# CameraSmartWatch.net
KiCad netlist of a schematic drawn in EasyEDA Pro
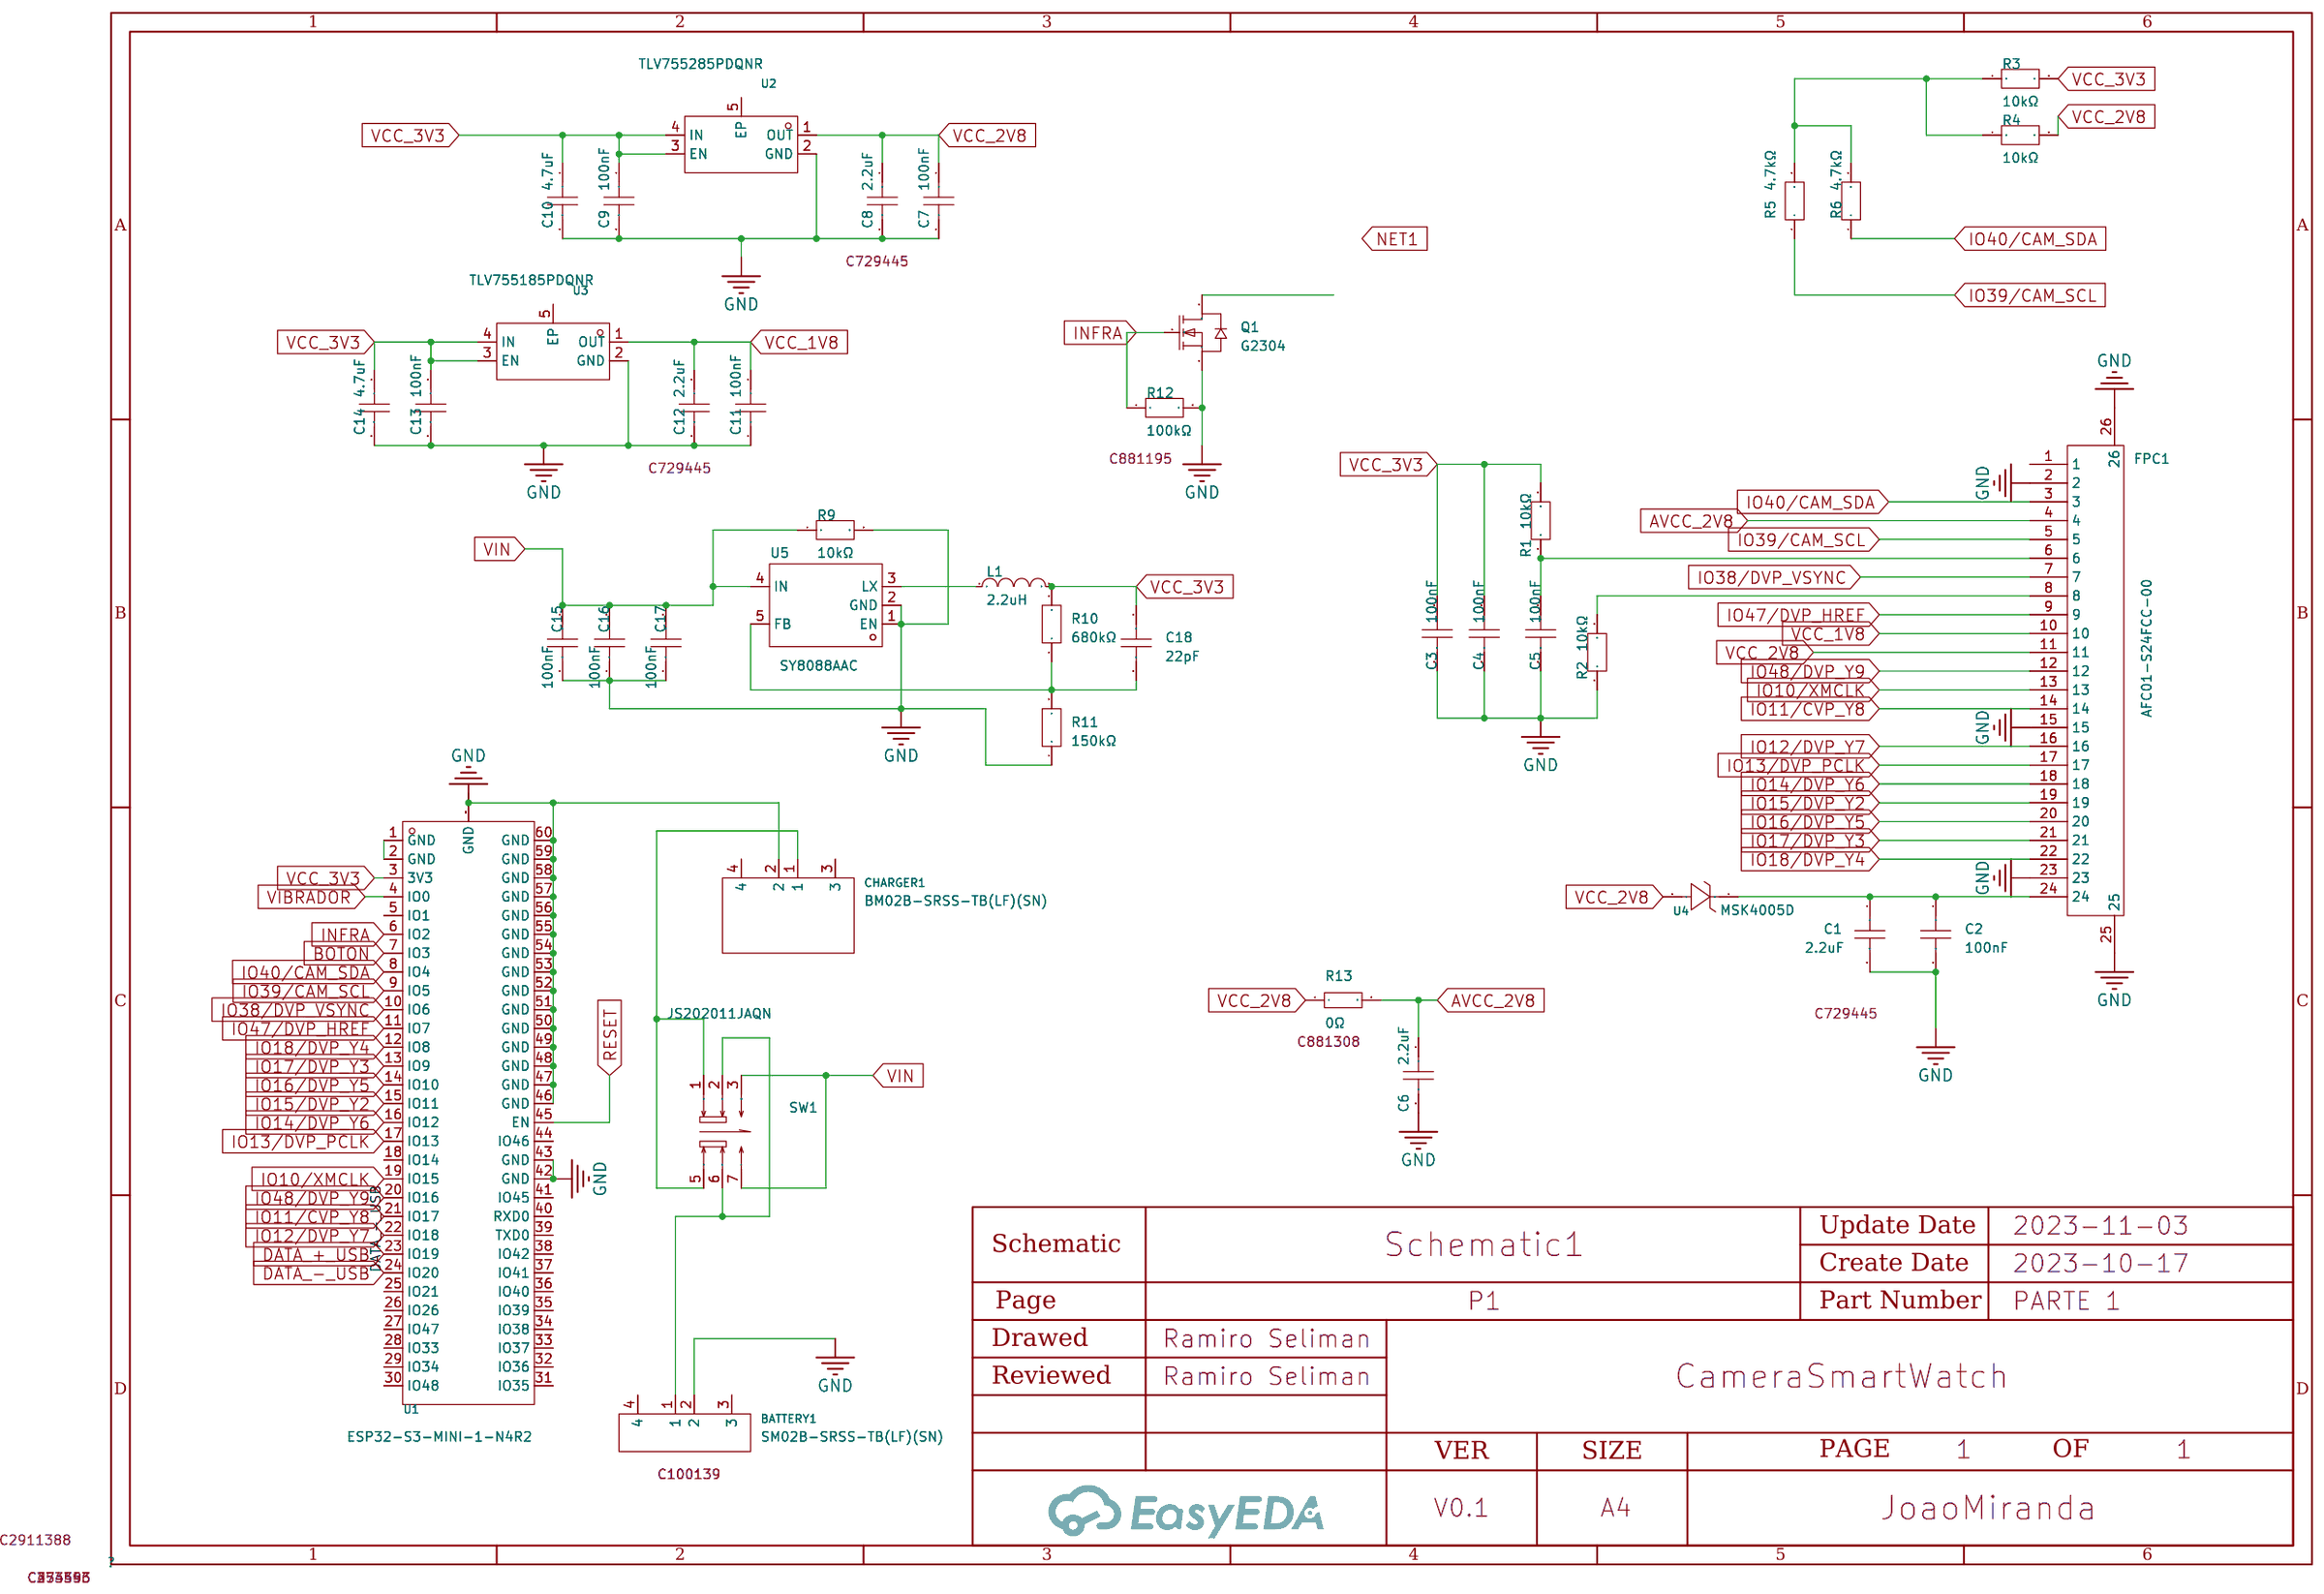
[diagram p0: schematic sheet]

(export (version "E")
  (design (tool "Eeschema 10.0.6"))
  (components
    (comp (ref "BATTERY1")
      (value "SM02B-SRSS-TB(LF)(SN)")
      (footprint "easyedapro:CONN-SMD_2P-P1.00_SM02B-SRSS-TB-LF-SN")
      (fields (field (name "Manufacturer") "JST"))
      (libsource (lib "easyedapro") (part "SM02B-SRSS-TB (LF)(SN)"))
    )
    (comp (ref "C1")
      (value "2.2uF")
      (footprint "easyedapro:C0201")
      (fields
        (field (name "Manufacturer Part") "C0201X5R225M100NT")
        (field (name "Manufacturer") "SANYEAR(叁叶源)")
        (field (name "Supplier Part") "C729445")
      )
      (libsource (lib "easyedapro") (part "CAP"))
    )
    (comp (ref "C2")
      (value "100nF")
      (footprint "easyedapro:C0201")
      (fields
        (field (name "Manufacturer Part") "C0201B104K016TSF")
        (field (name "Manufacturer") "IHHEC(禾伸堂)")
      )
      (libsource (lib "easyedapro") (part "CAP"))
    )
    (comp (ref "C3")
      (value "100nF")
      (footprint "easyedapro:C0201")
      (fields
        (field (name "Manufacturer Part") "C0201B104K016TSF")
        (field (name "Manufacturer") "IHHEC(禾伸堂)")
      )
      (libsource (lib "easyedapro") (part "CAP"))
    )
    (comp (ref "C4")
      (value "100nF")
      (footprint "easyedapro:C0201")
      (fields
        (field (name "Manufacturer Part") "C0201B104K016TSF")
        (field (name "Manufacturer") "IHHEC(禾伸堂)")
      )
      (libsource (lib "easyedapro") (part "CAP"))
    )
    (comp (ref "C5")
      (value "100nF")
      (footprint "easyedapro:C0201")
      (fields
        (field (name "Manufacturer Part") "C0201B104K016TSF")
        (field (name "Manufacturer") "IHHEC(禾伸堂)")
      )
      (libsource (lib "easyedapro") (part "CAP"))
    )
    (comp (ref "C6")
      (value "2.2uF")
      (footprint "easyedapro:C0201")
      (fields
        (field (name "Manufacturer Part") "C0201X5R225M100NT")
        (field (name "Manufacturer") "SANYEAR(叁叶源)")
      )
      (libsource (lib "easyedapro") (part "CAP"))
    )
    (comp (ref "C7")
      (value "100nF")
      (footprint "easyedapro:C0201")
      (fields
        (field (name "Manufacturer Part") "C0201B104K016TSF")
        (field (name "Manufacturer") "IHHEC(禾伸堂)")
      )
      (libsource (lib "easyedapro") (part "CAP"))
    )
    (comp (ref "C8")
      (value "2.2uF")
      (footprint "easyedapro:C0201")
      (fields
        (field (name "Manufacturer Part") "C0201X5R225M100NT")
        (field (name "Manufacturer") "SANYEAR(叁叶源)")
        (field (name "Supplier Part") "C729445")
      )
      (libsource (lib "easyedapro") (part "CAP"))
    )
    (comp (ref "C9")
      (value "100nF")
      (footprint "easyedapro:C0201")
      (fields
        (field (name "Manufacturer Part") "C0201B104K016TSF")
        (field (name "Manufacturer") "IHHEC(禾伸堂)")
      )
      (libsource (lib "easyedapro") (part "CAP"))
    )
    (comp (ref "C10")
      (value "4.7uF")
      (footprint "easyedapro:C0201")
      (fields
        (field (name "Manufacturer Part") "C0402X5R475M250NT")
        (field (name "Manufacturer") "SANYEAR(叁叶源)")
        (field (name "Supplier Part") "C2911388")
      )
      (libsource (lib "easyedapro") (part "CAP"))
    )
    (comp (ref "C11")
      (value "100nF")
      (footprint "easyedapro:C0201")
      (fields
        (field (name "Manufacturer Part") "C0201B104K016TSF")
        (field (name "Manufacturer") "IHHEC(禾伸堂)")
      )
      (libsource (lib "easyedapro") (part "CAP"))
    )
    (comp (ref "C12")
      (value "2.2uF")
      (footprint "easyedapro:C0201")
      (fields
        (field (name "Manufacturer Part") "C0201X5R225M100NT")
        (field (name "Manufacturer") "SANYEAR(叁叶源)")
        (field (name "Supplier Part") "C729445")
      )
      (libsource (lib "easyedapro") (part "CAP"))
    )
    (comp (ref "C13")
      (value "100nF")
      (footprint "easyedapro:C0201")
      (fields
        (field (name "Manufacturer Part") "C0201B104K016TSF")
        (field (name "Manufacturer") "IHHEC(禾伸堂)")
      )
      (libsource (lib "easyedapro") (part "CAP"))
    )
    (comp (ref "C14")
      (value "4.7uF")
      (footprint "easyedapro:C0201")
      (fields
        (field (name "Manufacturer Part") "C0402X5R475M250NT")
        (field (name "Manufacturer") "SANYEAR(叁叶源)")
        (field (name "Supplier Part") "C2911388")
      )
      (libsource (lib "easyedapro") (part "CAP"))
    )
    (comp (ref "C15")
      (value "100nF")
      (footprint "easyedapro:C0201")
      (fields
        (field (name "Manufacturer Part") "C0201B104K016TSF")
        (field (name "Manufacturer") "IHHEC(禾伸堂)")
      )
      (libsource (lib "easyedapro") (part "CAP"))
    )
    (comp (ref "C16")
      (value "100nF")
      (footprint "easyedapro:C0201")
      (fields
        (field (name "Manufacturer Part") "C0201B104K016TSF")
        (field (name "Manufacturer") "IHHEC(禾伸堂)")
      )
      (libsource (lib "easyedapro") (part "CAP"))
    )
    (comp (ref "C17")
      (value "100nF")
      (footprint "easyedapro:C0201")
      (fields
        (field (name "Manufacturer Part") "C0201B104K016TSF")
        (field (name "Manufacturer") "IHHEC(禾伸堂)")
      )
      (libsource (lib "easyedapro") (part "CAP"))
    )
    (comp (ref "C18")
      (value "22pF")
      (footprint "easyedapro:C0201")
      (fields
        (field (name "Manufacturer Part") "CC0201FRNPO8BN220")
        (field (name "Manufacturer") "YAGEO(国巨)")
      )
      (libsource (lib "easyedapro") (part "CAP"))
    )
    (comp (ref "CHARGER1")
      (value "BM02B-SRSS-TB(LF)(SN)")
      (footprint "easyedapro:CONN-TH_BM02B-SRSS-TB-LF-SN")
      (fields (field (name "Manufacturer") "JST"))
      (libsource (lib "easyedapro") (part "BM02B-SRSS-TB (LF)(SN)"))
    )
    (comp (ref "FPC1")
      (value "AFC01-S24FCC-00")
      (footprint "easyedapro:FPC-SMD_P0.5-24P_FGS-XJ-H2.0")
      (fields (field (name "Manufacturer") "JS(钜硕电子)"))
      (libsource (lib "easyedapro") (part "AFC01-S24FCC-00"))
    )
    (comp (ref "L1")
      (value "2.2uH")
      (footprint "easyedapro:L0603")
      (fields
        (field (name "Manufacturer Part") "CKCS252012-2.2uH/N")
        (field (name "Manufacturer") "CENKER(岑科)")
        (field (name "Supplier Part") "C354553")
      )
      (libsource (lib "easyedapro") (part "电感"))
    )
    (comp (ref "Q1")
      (value "G2304")
      (footprint "easyedapro:SOT-23-3_L2.9-W1.3-P1.90-LS2.4-BR")
      (fields (field (name "Manufacturer") "GOFORD(谷峰)"))
      (libsource (lib "easyedapro") (part "G2304"))
    )
    (comp (ref "R1")
      (value "10kΩ")
      (footprint "easyedapro:R0603")
      (description "Type: Resistance: Tolerance:±1% Tolerance:±1% Power(Watts):- Overload Voltage (Max):-")
      (fields (field (name "Manufacturer Part") "CR0201FH1002G") (field (name "Manufacturer") "LIZ(丽智电子)"))
      (libsource (lib "easyedapro") (part "CR0603F0R00P05Z"))
    )
    (comp (ref "R2")
      (value "10kΩ")
      (footprint "easyedapro:R0603")
      (description "Type: Resistance: Tolerance:±1% Tolerance:±1% Power(Watts):- Overload Voltage (Max):-")
      (fields (field (name "Manufacturer Part") "CR0201FH1002G") (field (name "Manufacturer") "LIZ(丽智电子)"))
      (libsource (lib "easyedapro") (part "CR0603F0R00P05Z"))
    )
    (comp (ref "R3")
      (value "10kΩ")
      (footprint "easyedapro:R0603")
      (description "Type: Resistance: Tolerance:±1% Tolerance:±1% Power(Watts):- Overload Voltage (Max):-")
      (fields (field (name "Manufacturer Part") "CR0201FH1002G") (field (name "Manufacturer") "LIZ(丽智电子)"))
      (libsource (lib "easyedapro") (part "CR0603F0R00P05Z"))
    )
    (comp (ref "R4")
      (value "10kΩ")
      (footprint "easyedapro:R0603")
      (description "Type: Resistance: Tolerance:±1% Tolerance:±1% Power(Watts):- Overload Voltage (Max):-")
      (fields (field (name "Manufacturer Part") "CR0201FH1002G") (field (name "Manufacturer") "LIZ(丽智电子)"))
      (libsource (lib "easyedapro") (part "CR0603F0R00P05Z"))
    )
    (comp (ref "R5")
      (value "4.7kΩ")
      (footprint "easyedapro:R0603")
      (fields
        (field (name "Manufacturer Part") "CR0201FH4701G")
        (field (name "Manufacturer") "LIZ(丽智电子)")
        (field (name "Supplier Part") "C100139")
      )
      (libsource (lib "easyedapro") (part "CR0603F0R00P05Z"))
    )
    (comp (ref "R6")
      (value "4.7kΩ")
      (footprint "easyedapro:R0603")
      (fields
        (field (name "Manufacturer Part") "CR0201FH4701G")
        (field (name "Manufacturer") "LIZ(丽智电子)")
        (field (name "Supplier Part") "C100139")
      )
      (libsource (lib "easyedapro") (part "CR0603F0R00P05Z"))
    )
    (comp (ref "R9")
      (value "10kΩ")
      (footprint "easyedapro:R0603")
      (description "Type: Resistance: Tolerance:±1% Tolerance:±1% Power(Watts):- Overload Voltage (Max):-")
      (fields (field (name "Manufacturer Part") "CR0201FH1002G") (field (name "Manufacturer") "LIZ(丽智电子)"))
      (libsource (lib "easyedapro") (part "CR0603F0R00P05Z"))
    )
    (comp (ref "R10")
      (value "680kΩ")
      (footprint "easyedapro:R0603")
      (fields
        (field (name "Manufacturer Part") "0201WMF6803TEE")
        (field (name "Manufacturer") "UNI-ROYAL(厚声)")
        (field (name "Supplier Part") "C473493")
      )
      (libsource (lib "easyedapro") (part "CR0603F0R00P05Z"))
    )
    (comp (ref "R11")
      (value "150kΩ")
      (footprint "easyedapro:R0603")
      (fields
        (field (name "Manufacturer Part") "RC0201FR-07150KL")
        (field (name "Manufacturer") "YAGEO(国巨)")
        (field (name "Supplier Part") "C274346")
      )
      (libsource (lib "easyedapro") (part "CR0603F0R00P05Z"))
    )
    (comp (ref "R12")
      (value "100kΩ")
      (footprint "easyedapro:R0603")
      (fields
        (field (name "Manufacturer Part") "CR0201J100KQ15Z")
        (field (name "Manufacturer") "EVER OHMS(天二科技)")
        (field (name "Supplier Part") "C881195")
      )
      (libsource (lib "easyedapro") (part "CR0603F0R00P05Z"))
    )
    (comp (ref "R13")
      (value "0Ω")
      (footprint "easyedapro:R0603")
      (fields
        (field (name "Manufacturer Part") "CR0603F0R00P05Z")
        (field (name "Manufacturer") "EVER OHMS(天二科技)")
        (field (name "Supplier Part") "C881308")
      )
      (libsource (lib "easyedapro") (part "Res"))
    )
    (comp (ref "SW1")
      (value "JS202011JAQN")
      (footprint "easyedapro:SW-SMD_JS202011JAQN")
      (fields (field (name "Manufacturer") "C&K"))
      (libsource (lib "easyedapro") (part "JS202011JAQN"))
    )
    (comp (ref "U1")
      (value "ESP32-S3-MINI-1-N4R2")
      (footprint "easyedapro:BULETM-SMD_ESP32-S3-MINI-1-N8")
      (fields (field (name "Manufacturer") "ESPRESSIF(乐鑫)"))
      (libsource (lib "easyedapro") (part "ESP32-S3-MINI-1-N4R2"))
    )
    (comp (ref "U2")
      (value "TLV755285PDQNR")
      (footprint "easyedapro:USPQ-4B04_L1.0-W1.0-P0.65-BL-EP")
      (fields (field (name "Manufacturer") "TI(德州仪器)"))
      (libsource (lib "easyedapro") (part "SGM2036S-2.8XXDH4G/TR"))
    )
    (comp (ref "U3")
      (value "TLV755185PDQNR")
      (footprint "easyedapro:USPQ-4B04_L1.0-W1.0-P0.65-BL-EP")
      (fields (field (name "Manufacturer") "TI(德州仪器)"))
      (libsource (lib "easyedapro") (part "SGM2036S-2.8XXDH4G/TR"))
    )
    (comp (ref "U4")
      (value "MSK4005D")
      (footprint "easyedapro:SOD-882_L1.0-W0.6-RD")
      (fields (field (name "Manufacturer") "SHIKUES(时科)"))
      (libsource (lib "easyedapro") (part "MSK4005D"))
    )
    (comp (ref "U5")
      (value "SY8088AAC")
      (footprint "easyedapro:SOT-23-5_L3.0-W1.7-P0.95-LS2.8-BR")
      (fields (field (name "Manufacturer") "silergy(矽力杰)"))
      (libsource (lib "easyedapro") (part "SY8088AAC"))
    )
  )
  (nets
    (net (code "1") (name "AVCC_2V8") (class "Default")
      (node (ref "C6") (pin "1") (pinfunction "1_1") (pintype "input"))
      (node (ref "FPC1") (pin "4") (pinfunction "4_4") (pintype "input"))
      (node (ref "R13") (pin "2") (pinfunction "2_2") (pintype "input"))
    )
    (net (code "2") (name "BOTON") (class "Default")
      (node (ref "U1") (pin "7") (pinfunction "IO3_7") (pintype "input"))
    )
    (net (code "3") (name "DATA_+_USB") (class "Default")
      (node (ref "U1") (pin "23") (pinfunction "IO19_23") (pintype "input"))
    )
    (net (code "4") (name "DATA_-_USB") (class "Default")
      (node (ref "U1") (pin "24") (pinfunction "IO20_24") (pintype "input"))
    )
    (net (code "5") (name "GND") (class "Default")
      (node (ref "BATTERY1") (pin "2") (pinfunction "2_2") (pintype "input"))
      (node (ref "C1") (pin "2") (pinfunction "2_2") (pintype "input"))
      (node (ref "C10") (pin "2") (pinfunction "2_2") (pintype "input"))
      (node (ref "C11") (pin "2") (pinfunction "2_2") (pintype "input"))
      (node (ref "C12") (pin "2") (pinfunction "2_2") (pintype "input"))
      (node (ref "C13") (pin "2") (pinfunction "2_2") (pintype "input"))
      (node (ref "C14") (pin "2") (pinfunction "2_2") (pintype "input"))
      (node (ref "C15") (pin "2") (pinfunction "2_2") (pintype "input"))
      (node (ref "C16") (pin "1") (pinfunction "1_1") (pintype "input"))
      (node (ref "C17") (pin "1") (pinfunction "1_1") (pintype "input"))
      (node (ref "C2") (pin "2") (pinfunction "2_2") (pintype "input"))
      (node (ref "C3") (pin "2") (pinfunction "2_2") (pintype "input"))
      (node (ref "C4") (pin "2") (pinfunction "2_2") (pintype "input"))
      (node (ref "C5") (pin "2") (pinfunction "2_2") (pintype "input"))
      (node (ref "C6") (pin "2") (pinfunction "2_2") (pintype "input"))
      (node (ref "C7") (pin "2") (pinfunction "2_2") (pintype "input"))
      (node (ref "C8") (pin "2") (pinfunction "2_2") (pintype "input"))
      (node (ref "C9") (pin "2") (pinfunction "2_2") (pintype "input"))
      (node (ref "CHARGER1") (pin "2") (pinfunction "2_2") (pintype "input"))
      (node (ref "FPC1") (pin "15") (pinfunction "15_15") (pintype "input"))
      (node (ref "FPC1") (pin "2") (pinfunction "2_2") (pintype "input"))
      (node (ref "FPC1") (pin "23") (pinfunction "23_23") (pintype "input"))
      (node (ref "FPC1") (pin "25") (pinfunction "25_25") (pintype "input"))
      (node (ref "FPC1") (pin "26") (pinfunction "26_26") (pintype "input"))
      (node (ref "Q1") (pin "2") (pinfunction "S_2") (pintype "input"))
      (node (ref "R11") (pin "1") (pinfunction "1_1") (pintype "input"))
      (node (ref "R12") (pin "2") (pinfunction "2_2") (pintype "input"))
      (node (ref "R2") (pin "1") (pinfunction "1_1") (pintype "input"))
      (node (ref "R9") (pin "2") (pinfunction "2_2") (pintype "input"))
      (node (ref "U1") (pin "42") (pinfunction "GND_42") (pintype "input"))
      (node (ref "U1") (pin "43") (pinfunction "GND_43") (pintype "input"))
      (node (ref "U1") (pin "46") (pinfunction "GND_46") (pintype "input"))
      (node (ref "U1") (pin "47") (pinfunction "GND_47") (pintype "input"))
      (node (ref "U1") (pin "48") (pinfunction "GND_48") (pintype "input"))
      (node (ref "U1") (pin "49") (pinfunction "GND_49") (pintype "input"))
      (node (ref "U1") (pin "50") (pinfunction "GND_50") (pintype "input"))
      (node (ref "U1") (pin "51") (pinfunction "GND_51") (pintype "input"))
      (node (ref "U1") (pin "52") (pinfunction "GND_52") (pintype "input"))
      (node (ref "U1") (pin "53") (pinfunction "GND_53") (pintype "input"))
      (node (ref "U1") (pin "54") (pinfunction "GND_54") (pintype "input"))
      (node (ref "U1") (pin "55") (pinfunction "GND_55") (pintype "input"))
      (node (ref "U1") (pin "56") (pinfunction "GND_56") (pintype "input"))
      (node (ref "U1") (pin "57") (pinfunction "GND_57") (pintype "input"))
      (node (ref "U1") (pin "58") (pinfunction "GND_58") (pintype "input"))
      (node (ref "U1") (pin "59") (pinfunction "GND_59") (pintype "input"))
      (node (ref "U1") (pin "60") (pinfunction "GND_60") (pintype "input"))
      (node (ref "U1") (pin "GND") (pinfunction "GND_GND") (pintype "input"))
      (node (ref "U2") (pin "2") (pinfunction "GND_2") (pintype "input"))
      (node (ref "U3") (pin "2") (pinfunction "GND_2") (pintype "input"))
      (node (ref "U5") (pin "1") (pinfunction "EN_1") (pintype "input"))
      (node (ref "U5") (pin "2") (pinfunction "GND_2") (pintype "input"))
    )
    (net (code "6") (name "INFRA") (class "Default")
      (node (ref "Q1") (pin "1") (pinfunction "G_1") (pintype "input"))
      (node (ref "R12") (pin "1") (pinfunction "1_1") (pintype "input"))
      (node (ref "U1") (pin "6") (pinfunction "IO2_6") (pintype "input"))
    )
    (net (code "7") (name "IO10{slash}XMCLK") (class "Default")
      (node (ref "FPC1") (pin "13") (pinfunction "13_13") (pintype "input"))
      (node (ref "U1") (pin "19") (pinfunction "IO15_19") (pintype "input"))
    )
    (net (code "8") (name "IO11{slash}CVP_Y8") (class "Default")
      (node (ref "FPC1") (pin "14") (pinfunction "14_14") (pintype "input"))
      (node (ref "U1") (pin "21") (pinfunction "IO17_21") (pintype "input"))
    )
    (net (code "9") (name "IO12{slash}DVP_Y7") (class "Default")
      (node (ref "FPC1") (pin "16") (pinfunction "16_16") (pintype "input"))
      (node (ref "U1") (pin "22") (pinfunction "IO18_22") (pintype "input"))
    )
    (net (code "10") (name "IO13{slash}DVP_PCLK") (class "Default")
      (node (ref "FPC1") (pin "17") (pinfunction "17_17") (pintype "input"))
      (node (ref "U1") (pin "17") (pinfunction "IO13_17") (pintype "input"))
    )
    (net (code "11") (name "IO14{slash}DVP_Y6") (class "Default")
      (node (ref "FPC1") (pin "18") (pinfunction "18_18") (pintype "input"))
      (node (ref "U1") (pin "16") (pinfunction "IO12_16") (pintype "input"))
    )
    (net (code "12") (name "IO15{slash}DVP_Y2") (class "Default")
      (node (ref "FPC1") (pin "19") (pinfunction "19_19") (pintype "input"))
      (node (ref "U1") (pin "15") (pinfunction "IO11_15") (pintype "input"))
    )
    (net (code "13") (name "IO16{slash}DVP_Y5") (class "Default")
      (node (ref "FPC1") (pin "20") (pinfunction "20_20") (pintype "input"))
      (node (ref "U1") (pin "14") (pinfunction "IO10_14") (pintype "input"))
    )
    (net (code "14") (name "IO17{slash}DVP_Y3") (class "Default")
      (node (ref "FPC1") (pin "21") (pinfunction "21_21") (pintype "input"))
      (node (ref "U1") (pin "13") (pinfunction "IO9_13") (pintype "input"))
    )
    (net (code "15") (name "IO18{slash}DVP_Y4") (class "Default")
      (node (ref "FPC1") (pin "22") (pinfunction "22_22") (pintype "input"))
      (node (ref "U1") (pin "12") (pinfunction "IO8_12") (pintype "input"))
    )
    (net (code "16") (name "IO38{slash}DVP_VSYNC") (class "Default")
      (node (ref "FPC1") (pin "7") (pinfunction "7_7") (pintype "input"))
      (node (ref "U1") (pin "10") (pinfunction "IO6_10") (pintype "input"))
    )
    (net (code "17") (name "IO39{slash}CAM_SCL") (class "Default")
      (node (ref "FPC1") (pin "5") (pinfunction "5_5") (pintype "input"))
      (node (ref "R5") (pin "1") (pinfunction "1_1") (pintype "input"))
      (node (ref "U1") (pin "9") (pinfunction "IO5_9") (pintype "input"))
    )
    (net (code "18") (name "IO40{slash}CAM_SDA") (class "Default")
      (node (ref "FPC1") (pin "3") (pinfunction "3_3") (pintype "input"))
      (node (ref "R6") (pin "1") (pinfunction "1_1") (pintype "input"))
      (node (ref "U1") (pin "8") (pinfunction "IO4_8") (pintype "input"))
    )
    (net (code "19") (name "IO47{slash}DVP_HREF") (class "Default")
      (node (ref "FPC1") (pin "9") (pinfunction "9_9") (pintype "input"))
      (node (ref "U1") (pin "11") (pinfunction "IO7_11") (pintype "input"))
    )
    (net (code "20") (name "IO48{slash}DVP_Y9") (class "Default")
      (node (ref "FPC1") (pin "12") (pinfunction "12_12") (pintype "input"))
      (node (ref "U1") (pin "20") (pinfunction "IO16_20") (pintype "input"))
    )
    (net (code "22") (name "Net-(BATTERY1-Pad1)") (class "Default")
      (node (ref "BATTERY1") (pin "1") (pinfunction "1_1") (pintype "input"))
      (node (ref "SW1") (pin "2") (pinfunction "2_2") (pintype "input"))
      (node (ref "SW1") (pin "6") (pinfunction "6_6") (pintype "input"))
    )
    (net (code "23") (name "Net-(C5-Pad1)") (class "Default")
      (node (ref "C5") (pin "1") (pinfunction "1_1") (pintype "input"))
      (node (ref "FPC1") (pin "6") (pinfunction "6_6") (pintype "input"))
      (node (ref "R1") (pin "1") (pinfunction "1_1") (pintype "input"))
    )
    (net (code "24") (name "Net-(CHARGER1-Pad1)") (class "Default")
      (node (ref "CHARGER1") (pin "1") (pinfunction "1_1") (pintype "input"))
      (node (ref "SW1") (pin "1") (pinfunction "1_1") (pintype "input"))
      (node (ref "SW1") (pin "5") (pinfunction "5_5") (pintype "input"))
    )
    (net (code "25") (name "Net-(FPC1-Pad8)") (class "Default")
      (node (ref "FPC1") (pin "8") (pinfunction "8_8") (pintype "input"))
      (node (ref "R2") (pin "2") (pinfunction "2_2") (pintype "input"))
    )
    (net (code "26") (name "Net-(R3-Pad1)") (class "Default")
      (node (ref "R3") (pin "1") (pinfunction "1_1") (pintype "input"))
      (node (ref "R4") (pin "1") (pinfunction "1_1") (pintype "input"))
      (node (ref "R5") (pin "2") (pinfunction "2_2") (pintype "input"))
      (node (ref "R6") (pin "2") (pinfunction "2_2") (pintype "input"))
    )
    (net (code "27") (name "Net-(U1-GND-Pad1)") (class "Default")
      (node (ref "U1") (pin "1") (pinfunction "GND_1") (pintype "input"))
      (node (ref "U1") (pin "2") (pinfunction "GND_2") (pintype "input"))
    )
    (net (code "28") (name "Net-(U4-K)") (class "Default")
      (node (ref "C1") (pin "1") (pinfunction "1_1") (pintype "input"))
      (node (ref "C2") (pin "1") (pinfunction "1_1") (pintype "input"))
      (node (ref "FPC1") (pin "24") (pinfunction "24_24") (pintype "input"))
      (node (ref "U4") (pin "1") (pinfunction "K_1") (pintype "input"))
    )
    (net (code "29") (name "Net-(U5-FB)") (class "Default")
      (node (ref "C18") (pin "2") (pinfunction "2_2") (pintype "input"))
      (node (ref "R10") (pin "1") (pinfunction "1_1") (pintype "input"))
      (node (ref "R11") (pin "2") (pinfunction "2_2") (pintype "input"))
      (node (ref "U5") (pin "5") (pinfunction "FB_5") (pintype "input"))
    )
    (net (code "30") (name "Net-(U5-LX)") (class "Default")
      (node (ref "L1") (pin "1") (pinfunction "1_1") (pintype "input"))
      (node (ref "U5") (pin "3") (pinfunction "LX_3") (pintype "input"))
    )
    (net (code "31") (name "RESET") (class "Default")
      (node (ref "U1") (pin "45") (pinfunction "EN_45") (pintype "input"))
    )
    (net (code "32") (name "VCC_1V8") (class "Default")
      (node (ref "C11") (pin "1") (pinfunction "1_1") (pintype "input"))
      (node (ref "C12") (pin "1") (pinfunction "1_1") (pintype "input"))
      (node (ref "FPC1") (pin "10") (pinfunction "10_10") (pintype "input"))
      (node (ref "U3") (pin "1") (pinfunction "OUT_1") (pintype "input"))
    )
    (net (code "33") (name "VCC_2V8") (class "Default")
      (node (ref "C7") (pin "1") (pinfunction "1_1") (pintype "input"))
      (node (ref "C8") (pin "1") (pinfunction "1_1") (pintype "input"))
      (node (ref "FPC1") (pin "11") (pinfunction "11_11") (pintype "input"))
      (node (ref "R13") (pin "1") (pinfunction "1_1") (pintype "input"))
      (node (ref "R4") (pin "2") (pinfunction "2_2") (pintype "input"))
      (node (ref "U2") (pin "1") (pinfunction "OUT_1") (pintype "input"))
      (node (ref "U4") (pin "2") (pinfunction "A_2") (pintype "input"))
    )
    (net (code "34") (name "VCC_3V3") (class "Default")
      (node (ref "C10") (pin "1") (pinfunction "1_1") (pintype "input"))
      (node (ref "C13") (pin "1") (pinfunction "1_1") (pintype "input"))
      (node (ref "C14") (pin "1") (pinfunction "1_1") (pintype "input"))
      (node (ref "C18") (pin "1") (pinfunction "1_1") (pintype "input"))
      (node (ref "C3") (pin "1") (pinfunction "1_1") (pintype "input"))
      (node (ref "C4") (pin "1") (pinfunction "1_1") (pintype "input"))
      (node (ref "C9") (pin "1") (pinfunction "1_1") (pintype "input"))
      (node (ref "L1") (pin "2") (pinfunction "2_2") (pintype "input"))
      (node (ref "R1") (pin "2") (pinfunction "2_2") (pintype "input"))
      (node (ref "R10") (pin "2") (pinfunction "2_2") (pintype "input"))
      (node (ref "R3") (pin "2") (pinfunction "2_2") (pintype "input"))
      (node (ref "U1") (pin "3") (pinfunction "3V3_3") (pintype "input"))
      (node (ref "U2") (pin "3") (pinfunction "EN_3") (pintype "input"))
      (node (ref "U2") (pin "4") (pinfunction "IN_4") (pintype "input"))
      (node (ref "U3") (pin "3") (pinfunction "EN_3") (pintype "input"))
      (node (ref "U3") (pin "4") (pinfunction "IN_4") (pintype "input"))
    )
    (net (code "35") (name "VIBRADOR") (class "Default")
      (node (ref "U1") (pin "4") (pinfunction "IO0_4") (pintype "input"))
    )
    (net (code "36") (name "VIN") (class "Default")
      (node (ref "C15") (pin "1") (pinfunction "1_1") (pintype "input"))
      (node (ref "C16") (pin "2") (pinfunction "2_2") (pintype "input"))
      (node (ref "C17") (pin "2") (pinfunction "2_2") (pintype "input"))
      (node (ref "R9") (pin "1") (pinfunction "1_1") (pintype "input"))
      (node (ref "SW1") (pin "3") (pinfunction "3_3") (pintype "input"))
      (node (ref "SW1") (pin "7") (pinfunction "7_7") (pintype "input"))
      (node (ref "U5") (pin "4") (pinfunction "IN_4") (pintype "input"))
    )
    (net (code "37") (name "unconnected-(BATTERY1-Pad3)") (class "Default")
      (node (ref "BATTERY1") (pin "3") (pinfunction "3_3") (pintype "input"))
    )
    (net (code "38") (name "unconnected-(BATTERY1-Pad4)") (class "Default")
      (node (ref "BATTERY1") (pin "4") (pinfunction "4_4") (pintype "input"))
    )
    (net (code "39") (name "unconnected-(CHARGER1-Pad3)") (class "Default")
      (node (ref "CHARGER1") (pin "3") (pinfunction "3_3") (pintype "input"))
    )
    (net (code "40") (name "unconnected-(CHARGER1-Pad4)") (class "Default")
      (node (ref "CHARGER1") (pin "4") (pinfunction "4_4") (pintype "input"))
    )
    (net (code "41") (name "unconnected-(FPC1-Pad1)") (class "Default")
      (node (ref "FPC1") (pin "1") (pinfunction "1_1") (pintype "input"))
    )
    (net (code "42") (name "unconnected-(Q1-D-Pad3)") (class "Default")
      (node (ref "Q1") (pin "3") (pinfunction "D_3") (pintype "input"))
    )
    (net (code "43") (name "unconnected-(U1-IO1-Pad5)") (class "Default")
      (node (ref "U1") (pin "5") (pinfunction "IO1_5") (pintype "input"))
    )
    (net (code "44") (name "unconnected-(U1-IO14-Pad18)") (class "Default")
      (node (ref "U1") (pin "18") (pinfunction "IO14_18") (pintype "input"))
    )
    (net (code "45") (name "unconnected-(U1-IO21-Pad25)") (class "Default")
      (node (ref "U1") (pin "25") (pinfunction "IO21_25") (pintype "input"))
    )
    (net (code "46") (name "unconnected-(U1-IO26-Pad26)") (class "Default")
      (node (ref "U1") (pin "26") (pinfunction "IO26_26") (pintype "input"))
    )
    (net (code "47") (name "unconnected-(U1-IO33-Pad28)") (class "Default")
      (node (ref "U1") (pin "28") (pinfunction "IO33_28") (pintype "input"))
    )
    (net (code "48") (name "unconnected-(U1-IO34-Pad29)") (class "Default")
      (node (ref "U1") (pin "29") (pinfunction "IO34_29") (pintype "input"))
    )
    (net (code "49") (name "unconnected-(U1-IO35-Pad31)") (class "Default")
      (node (ref "U1") (pin "31") (pinfunction "IO35_31") (pintype "input"))
    )
    (net (code "50") (name "unconnected-(U1-IO36-Pad32)") (class "Default")
      (node (ref "U1") (pin "32") (pinfunction "IO36_32") (pintype "input"))
    )
    (net (code "51") (name "unconnected-(U1-IO37-Pad33)") (class "Default")
      (node (ref "U1") (pin "33") (pinfunction "IO37_33") (pintype "input"))
    )
    (net (code "52") (name "unconnected-(U1-IO38-Pad34)") (class "Default")
      (node (ref "U1") (pin "34") (pinfunction "IO38_34") (pintype "input"))
    )
    (net (code "53") (name "unconnected-(U1-IO39-Pad35)") (class "Default")
      (node (ref "U1") (pin "35") (pinfunction "IO39_35") (pintype "input"))
    )
    (net (code "54") (name "unconnected-(U1-IO40-Pad36)") (class "Default")
      (node (ref "U1") (pin "36") (pinfunction "IO40_36") (pintype "input"))
    )
    (net (code "55") (name "unconnected-(U1-IO41-Pad37)") (class "Default")
      (node (ref "U1") (pin "37") (pinfunction "IO41_37") (pintype "input"))
    )
    (net (code "56") (name "unconnected-(U1-IO42-Pad38)") (class "Default")
      (node (ref "U1") (pin "38") (pinfunction "IO42_38") (pintype "input"))
    )
    (net (code "57") (name "unconnected-(U1-IO45-Pad41)") (class "Default")
      (node (ref "U1") (pin "41") (pinfunction "IO45_41") (pintype "input"))
    )
    (net (code "58") (name "unconnected-(U1-IO46-Pad44)") (class "Default")
      (node (ref "U1") (pin "44") (pinfunction "IO46_44") (pintype "input"))
    )
    (net (code "59") (name "unconnected-(U1-IO47-Pad27)") (class "Default")
      (node (ref "U1") (pin "27") (pinfunction "IO47_27") (pintype "input"))
    )
    (net (code "60") (name "unconnected-(U1-IO48-Pad30)") (class "Default")
      (node (ref "U1") (pin "30") (pinfunction "IO48_30") (pintype "input"))
    )
    (net (code "61") (name "unconnected-(U1-RXD0-Pad40)") (class "Default")
      (node (ref "U1") (pin "40") (pinfunction "RXD0_40") (pintype "input"))
    )
    (net (code "62") (name "unconnected-(U1-TXD0-Pad39)") (class "Default")
      (node (ref "U1") (pin "39") (pinfunction "TXD0_39") (pintype "input"))
    )
    (net (code "63") (name "unconnected-(U2-EP-Pad5)") (class "Default")
      (node (ref "U2") (pin "5") (pinfunction "EP_5") (pintype "input"))
    )
    (net (code "64") (name "unconnected-(U3-EP-Pad5)") (class "Default")
      (node (ref "U3") (pin "5") (pinfunction "EP_5") (pintype "input"))
    )
  )
)
